# spi_tiny_usb.net
KiCad netlist of a schematic drawn in EAGLE
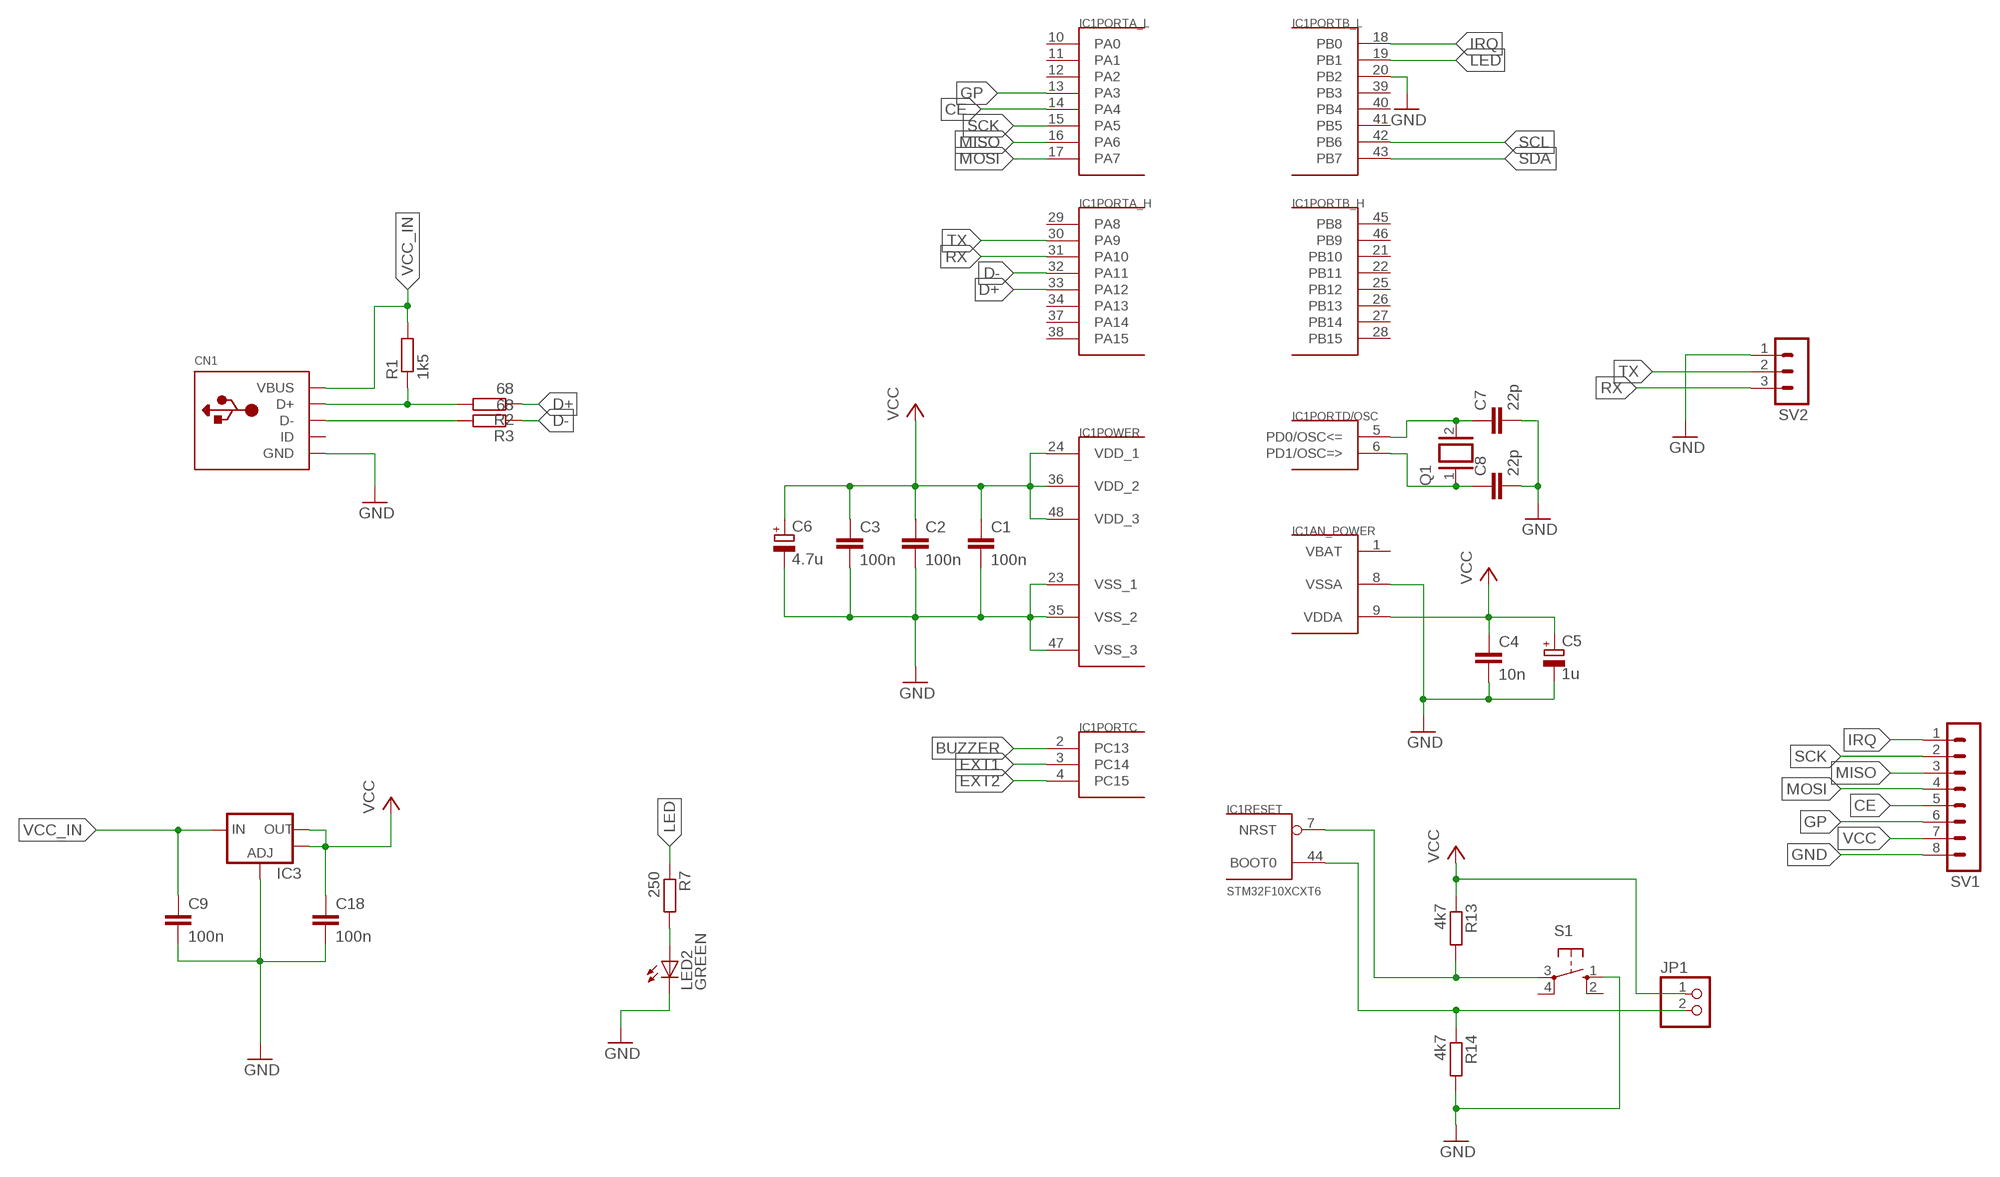
[diagram p0: schematic, sheet 1]

(export (version "E")
  (design (tool "Eeschema 10.0.6"))
  (components
    (comp (ref "C1")
      (value "100n")
      (footprint "eagle-import:C0805")
      (libsource (lib "eagle-import") (part "C-EUC0805"))
    )
    (comp (ref "C2")
      (value "100n")
      (footprint "eagle-import:C0805")
      (libsource (lib "eagle-import") (part "C-EUC0805"))
    )
    (comp (ref "C3")
      (value "100n")
      (footprint "eagle-import:C0805")
      (libsource (lib "eagle-import") (part "C-EUC0805"))
    )
    (comp (ref "C4")
      (value "10n")
      (footprint "eagle-import:C0805")
      (libsource (lib "eagle-import") (part "C-EUC0805"))
    )
    (comp (ref "C5")
      (value "1u")
      (footprint "eagle-import:153CLV-0505")
      (libsource (lib "eagle-import") (part "CPOL-EU153CLV-0505"))
    )
    (comp (ref "C6")
      (value "4.7u")
      (footprint "eagle-import:153CLV-0505")
      (libsource (lib "eagle-import") (part "CPOL-EU153CLV-0505"))
    )
    (comp (ref "C7")
      (value "22p")
      (footprint "eagle-import:C0805")
      (libsource (lib "eagle-import") (part "C-EUC0805"))
    )
    (comp (ref "C8")
      (value "22p")
      (footprint "eagle-import:C0805")
      (libsource (lib "eagle-import") (part "C-EUC0805"))
    )
    (comp (ref "C9")
      (value "100n")
      (footprint "eagle-import:C0805")
      (libsource (lib "eagle-import") (part "C-EUC0805"))
    )
    (comp (ref "C18")
      (value "100n")
      (footprint "eagle-import:C0805")
      (libsource (lib "eagle-import") (part "C-EUC0805"))
    )
    (comp (ref "CN1")
      (value "USBMINIB")
      (footprint "eagle-import:USB-MINIB")
      (libsource (lib "eagle-import") (part "USBMINIB"))
    )
    (comp (ref "IC1")
      (value "STM32F10XCXT6")
      (footprint "eagle-import:TQFP48")
      (libsource (lib "eagle-import") (part "STM32F10XCXT6"))
    )
    (comp (ref "IC3")
      (value "V_REG_LM1117SOT223")
      (footprint "eagle-import:SOT223")
      (libsource (lib "eagle-import") (part "V_REG_LM1117SOT223"))
    )
    (comp (ref "JP1")
      (value "PINHD-1X2")
      (footprint "eagle-import:1X02")
      (libsource (lib "eagle-import") (part "PINHD-1X2"))
    )
    (comp (ref "LED2")
      (value "GREEN")
      (footprint "eagle-import:CHIPLED_0805")
      (libsource (lib "eagle-import") (part "LEDCHIPLED_0805"))
    )
    (comp (ref "Q1")
      (value "XTAL/S")
      (footprint "eagle-import:QS")
      (libsource (lib "eagle-import") (part "XTAL/S"))
    )
    (comp (ref "R1")
      (value "1k5")
      (footprint "eagle-import:M1206")
      (libsource (lib "eagle-import") (part "R-EU_M1206"))
    )
    (comp (ref "R2")
      (value "68")
      (footprint "eagle-import:M0805")
      (libsource (lib "eagle-import") (part "R-EU_M0805"))
    )
    (comp (ref "R3")
      (value "68")
      (footprint "eagle-import:M0805")
      (libsource (lib "eagle-import") (part "R-EU_M0805"))
    )
    (comp (ref "R7")
      (value "250")
      (footprint "eagle-import:R0805")
      (libsource (lib "eagle-import") (part "resistor_R-EU_R0805"))
    )
    (comp (ref "R13")
      (value "4k7")
      (footprint "eagle-import:R0805")
      (libsource (lib "eagle-import") (part "R-EU_R0805"))
    )
    (comp (ref "R14")
      (value "4k7")
      (footprint "eagle-import:R1206")
      (libsource (lib "eagle-import") (part "R-EU_R1206"))
    )
    (comp (ref "S1")
      (value "10-XX")
      (footprint "eagle-import:B3F-10XX")
      (fields (field (name "MPN") "B3F-1000"))
      (libsource (lib "eagle-import") (part "10-XX"))
    )
    (comp (ref "SV1")
      (value "MA08-1")
      (footprint "eagle-import:MA08-1")
      (libsource (lib "eagle-import") (part "MA08-1"))
    )
    (comp (ref "SV2")
      (value "MA03-1")
      (footprint "eagle-import:MA03-1")
      (libsource (lib "eagle-import") (part "MA03-1"))
    )
  )
  (nets
    (net (code "1") (name "/VBAT") (class "Default")
      (node (ref "IC1") (pin "1") (pinfunction "VBAT_1") (pintype "power_in"))
    )
    (net (code "2") (name "BUZZER") (class "Default")
      (node (ref "IC1") (pin "2") (pinfunction "PC13_2") (pintype "bidirectional"))
    )
    (net (code "3") (name "CE") (class "Default")
      (node (ref "IC1") (pin "14") (pinfunction "PA4_14") (pintype "bidirectional"))
      (node (ref "SV1") (pin "5") (pinfunction "5_5") (pintype "passive"))
    )
    (net (code "4") (name "D+") (class "Default")
      (node (ref "IC1") (pin "33") (pinfunction "PA12_33") (pintype "bidirectional"))
      (node (ref "R2") (pin "1") (pinfunction "1_1") (pintype "passive"))
    )
    (net (code "5") (name "D-") (class "Default")
      (node (ref "IC1") (pin "32") (pinfunction "PA11_32") (pintype "bidirectional"))
      (node (ref "R3") (pin "1") (pinfunction "1_1") (pintype "passive"))
    )
    (net (code "6") (name "EXT1") (class "Default")
      (node (ref "IC1") (pin "3") (pinfunction "PC14_3") (pintype "bidirectional"))
    )
    (net (code "7") (name "EXT2") (class "Default")
      (node (ref "IC1") (pin "4") (pinfunction "PC15_4") (pintype "bidirectional"))
    )
    (net (code "8") (name "GND") (class "Default")
      (node (ref "C1") (pin "2") (pinfunction "2_2") (pintype "passive"))
      (node (ref "C18") (pin "2") (pinfunction "2_2") (pintype "passive"))
      (node (ref "C2") (pin "2") (pinfunction "2_2") (pintype "passive"))
      (node (ref "C3") (pin "2") (pinfunction "2_2") (pintype "passive"))
      (node (ref "C4") (pin "2") (pinfunction "2_2") (pintype "passive"))
      (node (ref "C5") (pin "-") (pinfunction "-_-") (pintype "passive"))
      (node (ref "C6") (pin "-") (pinfunction "-_-") (pintype "passive"))
      (node (ref "C7") (pin "2") (pinfunction "2_2") (pintype "passive"))
      (node (ref "C8") (pin "2") (pinfunction "2_2") (pintype "passive"))
      (node (ref "C9") (pin "2") (pinfunction "2_2") (pintype "passive"))
      (node (ref "CN1") (pin "GND") (pinfunction "GND_GND") (pintype "power_in"))
      (node (ref "IC1") (pin "20") (pinfunction "PB2_20") (pintype "bidirectional"))
      (node (ref "IC1") (pin "23") (pinfunction "VSS_1_23") (pintype "power_in"))
      (node (ref "IC1") (pin "35") (pinfunction "VSS_2_35") (pintype "power_in"))
      (node (ref "IC1") (pin "47") (pinfunction "VSS_3_47") (pintype "power_in"))
      (node (ref "IC1") (pin "8") (pinfunction "VSSA_8") (pintype "power_in"))
      (node (ref "IC3") (pin "1") (pinfunction "ADJ_1") (pintype "input"))
      (node (ref "LED2") (pin "C") (pinfunction "C_C") (pintype "passive"))
      (node (ref "R14") (pin "2") (pinfunction "2_2") (pintype "passive"))
      (node (ref "S1") (pin "1") (pinfunction "S_1") (pintype "passive"))
      (node (ref "SV1") (pin "8") (pinfunction "8_8") (pintype "passive"))
      (node (ref "SV2") (pin "1") (pinfunction "1_1") (pintype "passive"))
    )
    (net (code "9") (name "GP") (class "Default")
      (node (ref "IC1") (pin "13") (pinfunction "PA3_13") (pintype "bidirectional"))
      (node (ref "SV1") (pin "6") (pinfunction "6_6") (pintype "passive"))
    )
    (net (code "10") (name "IRQ") (class "Default")
      (node (ref "IC1") (pin "18") (pinfunction "PB0_18") (pintype "bidirectional"))
      (node (ref "SV1") (pin "1") (pinfunction "1_1") (pintype "passive"))
    )
    (net (code "11") (name "LED") (class "Default")
      (node (ref "IC1") (pin "19") (pinfunction "PB1_19") (pintype "bidirectional"))
      (node (ref "R7") (pin "1") (pinfunction "1_1") (pintype "passive"))
    )
    (net (code "12") (name "MISO") (class "Default")
      (node (ref "IC1") (pin "16") (pinfunction "PA6_16") (pintype "bidirectional"))
      (node (ref "SV1") (pin "3") (pinfunction "3_3") (pintype "passive"))
    )
    (net (code "13") (name "MOSI") (class "Default")
      (node (ref "IC1") (pin "17") (pinfunction "PA7_17") (pintype "bidirectional"))
      (node (ref "SV1") (pin "4") (pinfunction "4_4") (pintype "passive"))
    )
    (net (code "14") (name "Net-(CN1-PadD+)") (class "Default")
      (node (ref "CN1") (pin "D+") (pinfunction "D+_D+") (pintype "bidirectional"))
      (node (ref "R1") (pin "1") (pinfunction "1_1") (pintype "passive"))
      (node (ref "R2") (pin "2") (pinfunction "2_2") (pintype "passive"))
    )
    (net (code "15") (name "Net-(CN1-PadD-)") (class "Default")
      (node (ref "CN1") (pin "D-") (pinfunction "D-_D-") (pintype "bidirectional"))
      (node (ref "R3") (pin "2") (pinfunction "2_2") (pintype "passive"))
    )
    (net (code "16") (name "Net-(IC1G-PD0{slash}OSC<=)") (class "Default")
      (node (ref "C7") (pin "1") (pinfunction "1_1") (pintype "passive"))
      (node (ref "IC1") (pin "5") (pinfunction "PD0/OSC<=_5") (pintype "bidirectional"))
      (node (ref "Q1") (pin "2") (pinfunction "2_2") (pintype "passive"))
    )
    (net (code "17") (name "Net-(IC1G-PD1{slash}OSC=>)") (class "Default")
      (node (ref "C8") (pin "1") (pinfunction "1_1") (pintype "passive"))
      (node (ref "IC1") (pin "6") (pinfunction "PD1/OSC=>_6") (pintype "bidirectional"))
      (node (ref "Q1") (pin "1") (pinfunction "1_1") (pintype "passive"))
    )
    (net (code "18") (name "Net-(IC1I-BOOT0)") (class "Default")
      (node (ref "IC1") (pin "44") (pinfunction "BOOT0_44") (pintype "input"))
      (node (ref "JP1") (pin "2") (pinfunction "2_2") (pintype "passive"))
      (node (ref "R14") (pin "1") (pinfunction "1_1") (pintype "passive"))
    )
    (net (code "19") (name "Net-(IC1I-NRST)") (class "Default")
      (node (ref "IC1") (pin "7") (pinfunction "NRST_7") (pintype "input"))
      (node (ref "R13") (pin "2") (pinfunction "2_2") (pintype "passive"))
      (node (ref "S1") (pin "3") (pinfunction "P_3") (pintype "passive"))
    )
    (net (code "20") (name "Net-(LED2-PadA)") (class "Default")
      (node (ref "LED2") (pin "A") (pinfunction "A_A") (pintype "passive"))
      (node (ref "R7") (pin "2") (pinfunction "2_2") (pintype "passive"))
    )
    (net (code "21") (name "RX") (class "Default")
      (node (ref "IC1") (pin "31") (pinfunction "PA10_31") (pintype "bidirectional"))
      (node (ref "SV2") (pin "3") (pinfunction "3_3") (pintype "passive"))
    )
    (net (code "22") (name "SCK") (class "Default")
      (node (ref "IC1") (pin "15") (pinfunction "PA5_15") (pintype "bidirectional"))
      (node (ref "SV1") (pin "2") (pinfunction "2_2") (pintype "passive"))
    )
    (net (code "23") (name "SCL") (class "Default")
      (node (ref "IC1") (pin "42") (pinfunction "PB6_42") (pintype "bidirectional"))
    )
    (net (code "24") (name "SDA") (class "Default")
      (node (ref "IC1") (pin "43") (pinfunction "PB7_43") (pintype "bidirectional"))
    )
    (net (code "25") (name "TX") (class "Default")
      (node (ref "IC1") (pin "30") (pinfunction "PA9_30") (pintype "bidirectional"))
      (node (ref "SV2") (pin "2") (pinfunction "2_2") (pintype "passive"))
    )
    (net (code "26") (name "VCC") (class "Default")
      (node (ref "C1") (pin "1") (pinfunction "1_1") (pintype "passive"))
      (node (ref "C18") (pin "1") (pinfunction "1_1") (pintype "passive"))
      (node (ref "C2") (pin "1") (pinfunction "1_1") (pintype "passive"))
      (node (ref "C3") (pin "1") (pinfunction "1_1") (pintype "passive"))
      (node (ref "C4") (pin "1") (pinfunction "1_1") (pintype "passive"))
      (node (ref "C5") (pin "+") (pinfunction "+_+") (pintype "passive"))
      (node (ref "C6") (pin "+") (pinfunction "+_+") (pintype "passive"))
      (node (ref "IC1") (pin "24") (pinfunction "VDD_1_24") (pintype "power_in"))
      (node (ref "IC1") (pin "36") (pinfunction "VDD_2_36") (pintype "power_in"))
      (node (ref "IC1") (pin "48") (pinfunction "VDD_3_48") (pintype "power_in"))
      (node (ref "IC1") (pin "9") (pinfunction "VDDA_9") (pintype "power_in"))
      (node (ref "IC3") (pin "2") (pinfunction "OUT_2") (pintype "output"))
      (node (ref "IC3") (pin "4") (pinfunction "OUT_4") (pintype "output"))
      (node (ref "JP1") (pin "1") (pinfunction "1_1") (pintype "passive"))
      (node (ref "R13") (pin "1") (pinfunction "1_1") (pintype "passive"))
      (node (ref "SV1") (pin "7") (pinfunction "7_7") (pintype "passive"))
    )
    (net (code "27") (name "VCC_IN") (class "Default")
      (node (ref "C9") (pin "1") (pinfunction "1_1") (pintype "passive"))
      (node (ref "CN1") (pin "VBUS") (pinfunction "VBUS_VBUS") (pintype "power_in"))
      (node (ref "IC3") (pin "3") (pinfunction "IN_3") (pintype "input"))
      (node (ref "R1") (pin "2") (pinfunction "2_2") (pintype "passive"))
    )
    (net (code "28") (name "unconnected-(CN1-PadID)") (class "Default")
      (node (ref "CN1") (pin "ID") (pinfunction "ID_ID") (pintype "bidirectional"))
    )
    (net (code "29") (name "unconnected-(IC1B-PA8-Pad29)") (class "Default")
      (node (ref "IC1") (pin "29") (pinfunction "PA8_29") (pintype "bidirectional"))
    )
    (net (code "30") (name "unconnected-(IC1B-PA13-Pad34)") (class "Default")
      (node (ref "IC1") (pin "34") (pinfunction "PA13_34") (pintype "bidirectional"))
    )
    (net (code "31") (name "unconnected-(IC1B-PA14-Pad37)") (class "Default")
      (node (ref "IC1") (pin "37") (pinfunction "PA14_37") (pintype "bidirectional"))
    )
    (net (code "32") (name "unconnected-(IC1B-PA15-Pad38)") (class "Default")
      (node (ref "IC1") (pin "38") (pinfunction "PA15_38") (pintype "bidirectional"))
    )
    (net (code "33") (name "unconnected-(IC1C-PA0-Pad10)") (class "Default")
      (node (ref "IC1") (pin "10") (pinfunction "PA0_10") (pintype "bidirectional"))
    )
    (net (code "34") (name "unconnected-(IC1C-PA1-Pad11)") (class "Default")
      (node (ref "IC1") (pin "11") (pinfunction "PA1_11") (pintype "bidirectional"))
    )
    (net (code "35") (name "unconnected-(IC1C-PA2-Pad12)") (class "Default")
      (node (ref "IC1") (pin "12") (pinfunction "PA2_12") (pintype "bidirectional"))
    )
    (net (code "36") (name "unconnected-(IC1D-PB8-Pad45)") (class "Default")
      (node (ref "IC1") (pin "45") (pinfunction "PB8_45") (pintype "bidirectional"))
    )
    (net (code "37") (name "unconnected-(IC1D-PB9-Pad46)") (class "Default")
      (node (ref "IC1") (pin "46") (pinfunction "PB9_46") (pintype "bidirectional"))
    )
    (net (code "38") (name "unconnected-(IC1D-PB10-Pad21)") (class "Default")
      (node (ref "IC1") (pin "21") (pinfunction "PB10_21") (pintype "bidirectional"))
    )
    (net (code "39") (name "unconnected-(IC1D-PB11-Pad22)") (class "Default")
      (node (ref "IC1") (pin "22") (pinfunction "PB11_22") (pintype "bidirectional"))
    )
    (net (code "40") (name "unconnected-(IC1D-PB12-Pad25)") (class "Default")
      (node (ref "IC1") (pin "25") (pinfunction "PB12_25") (pintype "bidirectional"))
    )
    (net (code "41") (name "unconnected-(IC1D-PB13-Pad26)") (class "Default")
      (node (ref "IC1") (pin "26") (pinfunction "PB13_26") (pintype "bidirectional"))
    )
    (net (code "42") (name "unconnected-(IC1D-PB14-Pad27)") (class "Default")
      (node (ref "IC1") (pin "27") (pinfunction "PB14_27") (pintype "bidirectional"))
    )
    (net (code "43") (name "unconnected-(IC1D-PB15-Pad28)") (class "Default")
      (node (ref "IC1") (pin "28") (pinfunction "PB15_28") (pintype "bidirectional"))
    )
    (net (code "44") (name "unconnected-(IC1E-PB3-Pad39)") (class "Default")
      (node (ref "IC1") (pin "39") (pinfunction "PB3_39") (pintype "bidirectional"))
    )
    (net (code "45") (name "unconnected-(IC1E-PB4-Pad40)") (class "Default")
      (node (ref "IC1") (pin "40") (pinfunction "PB4_40") (pintype "bidirectional"))
    )
    (net (code "46") (name "unconnected-(IC1E-PB5-Pad41)") (class "Default")
      (node (ref "IC1") (pin "41") (pinfunction "PB5_41") (pintype "bidirectional"))
    )
    (net (code "47") (name "unconnected-(S1-P1-Pad4)") (class "Default")
      (node (ref "S1") (pin "4") (pinfunction "P1_4") (pintype "passive"))
    )
    (net (code "48") (name "unconnected-(S1-S1-Pad2)") (class "Default")
      (node (ref "S1") (pin "2") (pinfunction "S1_2") (pintype "passive"))
    )
  )
)
